# piezo-jfet-buffer-simple-2x.net
KiCad netlist of a schematic drawn in EAGLE
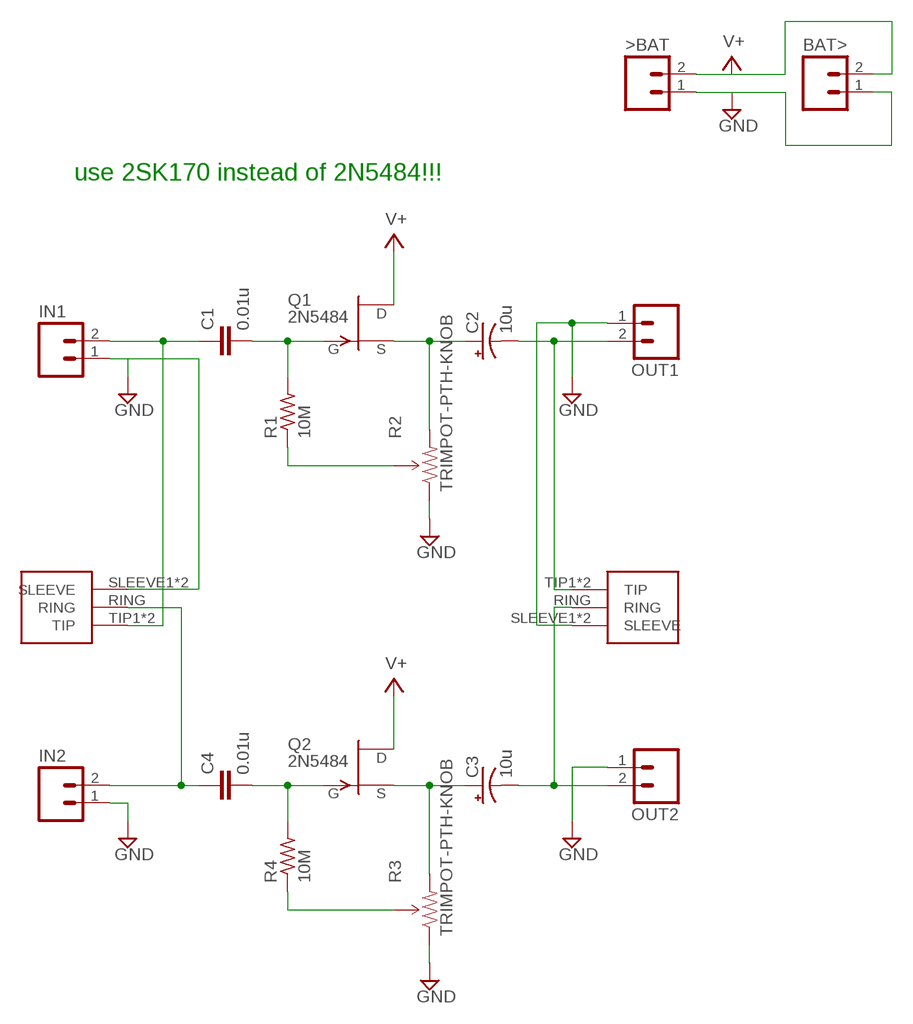
[diagram p0: schematic, sheet 1]

(export (version "E")
  (design (tool "Eeschema 10.0.6"))
  (components
    (comp (ref ">BAT")
      (value "M02PTH")
      (footprint "eagle-import:1X02")
      (libsource (lib "eagle-import") (part "M02PTH"))
    )
    (comp (ref "BAT>")
      (value "M02PTH")
      (footprint "eagle-import:1X02")
      (libsource (lib "eagle-import") (part "M02PTH"))
    )
    (comp (ref "C1")
      (value "0.01u")
      (footprint "eagle-import:C5B3")
      (libsource (lib "eagle-import") (part "C5/3"))
    )
    (comp (ref "C2")
      (value "10u")
      (footprint "eagle-import:CPOL-RADIAL-10UF-25V")
      (libsource (lib "eagle-import") (part "CAP_POLPTH2"))
    )
    (comp (ref "C3")
      (value "10u")
      (footprint "eagle-import:CPOL-RADIAL-10UF-25V")
      (libsource (lib "eagle-import") (part "CAP_POLPTH2"))
    )
    (comp (ref "C4")
      (value "0.01u")
      (footprint "eagle-import:C5B3")
      (libsource (lib "eagle-import") (part "C5/3"))
    )
    (comp (ref "IN1")
      (value "M02LOCK")
      (footprint "eagle-import:1X02_LOCK")
      (libsource (lib "eagle-import") (part "M02LOCK"))
    )
    (comp (ref "IN2")
      (value "M02LOCK")
      (footprint "eagle-import:1X02_LOCK")
      (libsource (lib "eagle-import") (part "M02LOCK"))
    )
    (comp (ref "OUT1")
      (value "M02LOCK")
      (footprint "eagle-import:1X02_LOCK")
      (libsource (lib "eagle-import") (part "M02LOCK"))
    )
    (comp (ref "OUT2")
      (value "M02LOCK")
      (footprint "eagle-import:1X02_LOCK")
      (libsource (lib "eagle-import") (part "M02LOCK"))
    )
    (comp (ref "Q1")
      (value "2N5484")
      (footprint "eagle-import:TO92-")
      (libsource (lib "eagle-import") (part "?5482N4"))
    )
    (comp (ref "Q2")
      (value "2N5484")
      (footprint "eagle-import:TO92-")
      (libsource (lib "eagle-import") (part "?5482N4"))
    )
    (comp (ref "R1")
      (value "10M")
      (footprint "eagle-import:0204V")
      (libsource (lib "eagle-import") (part "R-US_0204/2V"))
    )
    (comp (ref "R2")
      (value "TRIMPOT-PTH-KNOB")
      (footprint "eagle-import:3386U")
      (libsource (lib "eagle-import") (part "TRIMPOT-PTH-KNOB"))
    )
    (comp (ref "R3")
      (value "TRIMPOT-PTH-KNOB")
      (footprint "eagle-import:3386U")
      (libsource (lib "eagle-import") (part "TRIMPOT-PTH-KNOB"))
    )
    (comp (ref "R4")
      (value "10M")
      (footprint "eagle-import:0204V")
      (libsource (lib "eagle-import") (part "R-US_0204/2V"))
    )
    (comp (ref "U$1")
      (value "1/8\"-F-STEREO-PCB")
      (footprint "eagle-import:1_8_-F-STEREO-PCB")
      (libsource (lib "eagle-import") (part "1/8{dblquote}-F-STEREO-PCB"))
    )
    (comp (ref "U$2")
      (value "1/8\"-F-STEREO-PCB")
      (footprint "eagle-import:1_8_-F-STEREO-PCB")
      (libsource (lib "eagle-import") (part "1/8{dblquote}-F-STEREO-PCB"))
    )
  )
  (nets
    (net (code "1") (name "GND") (class "Default")
      (node (ref ">BAT") (pin "1") (pinfunction "1_1") (pintype "passive"))
      (node (ref "BAT>") (pin "1") (pinfunction "1_1") (pintype "passive"))
      (node (ref "IN1") (pin "1") (pinfunction "1_1") (pintype "passive"))
      (node (ref "IN2") (pin "1") (pinfunction "1_1") (pintype "passive"))
      (node (ref "OUT1") (pin "1") (pinfunction "1_1") (pintype "passive"))
      (node (ref "OUT2") (pin "1") (pinfunction "1_1") (pintype "passive"))
      (node (ref "R2") (pin "1") (pinfunction "CCW_1") (pintype "passive"))
      (node (ref "R3") (pin "1") (pinfunction "CCW_1") (pintype "passive"))
      (node (ref "U$1") (pin "SLEEVE1") (pinfunction "SLEEVE_SLEEVE1") (pintype "bidirectional"))
      (node (ref "U$1") (pin "SLEEVE2") (pinfunction "SLEEVE_SLEEVE2") (pintype "bidirectional"))
      (node (ref "U$2") (pin "SLEEVE1") (pinfunction "SLEEVE_SLEEVE1") (pintype "bidirectional"))
      (node (ref "U$2") (pin "SLEEVE2") (pinfunction "SLEEVE_SLEEVE2") (pintype "bidirectional"))
    )
    (net (code "2") (name "Net-(C1-Pad1)") (class "Default")
      (node (ref "C1") (pin "1") (pinfunction "1_1") (pintype "passive"))
      (node (ref "IN1") (pin "2") (pinfunction "2_2") (pintype "passive"))
      (node (ref "U$2") (pin "TIP1") (pinfunction "TIP_TIP1") (pintype "bidirectional"))
      (node (ref "U$2") (pin "TIP2") (pinfunction "TIP_TIP2") (pintype "bidirectional"))
    )
    (net (code "3") (name "Net-(C2-+)") (class "Default")
      (node (ref "C2") (pin "1") (pinfunction "+_1") (pintype "passive"))
      (node (ref "Q1") (pin "2") (pinfunction "S_2") (pintype "passive"))
      (node (ref "R2") (pin "3") (pinfunction "CW_3") (pintype "passive"))
    )
    (net (code "4") (name "Net-(C2--)") (class "Default")
      (node (ref "C2") (pin "2") (pinfunction "-_2") (pintype "passive"))
      (node (ref "OUT1") (pin "2") (pinfunction "2_2") (pintype "passive"))
      (node (ref "U$1") (pin "TIP1") (pinfunction "TIP_TIP1") (pintype "bidirectional"))
      (node (ref "U$1") (pin "TIP2") (pinfunction "TIP_TIP2") (pintype "bidirectional"))
    )
    (net (code "5") (name "Net-(C3-+)") (class "Default")
      (node (ref "C3") (pin "1") (pinfunction "+_1") (pintype "passive"))
      (node (ref "Q2") (pin "2") (pinfunction "S_2") (pintype "passive"))
      (node (ref "R3") (pin "3") (pinfunction "CW_3") (pintype "passive"))
    )
    (net (code "6") (name "Net-(C3--)") (class "Default")
      (node (ref "C3") (pin "2") (pinfunction "-_2") (pintype "passive"))
      (node (ref "OUT2") (pin "2") (pinfunction "2_2") (pintype "passive"))
      (node (ref "U$1") (pin "RING") (pinfunction "RING_RING") (pintype "bidirectional"))
    )
    (net (code "7") (name "Net-(C4-Pad1)") (class "Default")
      (node (ref "C4") (pin "1") (pinfunction "1_1") (pintype "passive"))
      (node (ref "IN2") (pin "2") (pinfunction "2_2") (pintype "passive"))
      (node (ref "U$2") (pin "RING") (pinfunction "RING_RING") (pintype "bidirectional"))
    )
    (net (code "8") (name "Net-(Q1-G)") (class "Default")
      (node (ref "C1") (pin "2") (pinfunction "2_2") (pintype "passive"))
      (node (ref "Q1") (pin "1") (pinfunction "G_1") (pintype "passive"))
      (node (ref "R1") (pin "2") (pinfunction "2_2") (pintype "passive"))
    )
    (net (code "9") (name "Net-(Q2-G)") (class "Default")
      (node (ref "C4") (pin "2") (pinfunction "2_2") (pintype "passive"))
      (node (ref "Q2") (pin "1") (pinfunction "G_1") (pintype "passive"))
      (node (ref "R4") (pin "2") (pinfunction "2_2") (pintype "passive"))
    )
    (net (code "10") (name "Net-(R2-WIPER)") (class "Default")
      (node (ref "R1") (pin "1") (pinfunction "1_1") (pintype "passive"))
      (node (ref "R2") (pin "2") (pinfunction "WIPER_2") (pintype "passive"))
    )
    (net (code "11") (name "Net-(R3-WIPER)") (class "Default")
      (node (ref "R3") (pin "2") (pinfunction "WIPER_2") (pintype "passive"))
      (node (ref "R4") (pin "1") (pinfunction "1_1") (pintype "passive"))
    )
    (net (code "12") (name "V+") (class "Default")
      (node (ref ">BAT") (pin "2") (pinfunction "2_2") (pintype "passive"))
      (node (ref "BAT>") (pin "2") (pinfunction "2_2") (pintype "passive"))
      (node (ref "Q1") (pin "3") (pinfunction "D_3") (pintype "passive"))
      (node (ref "Q2") (pin "3") (pinfunction "D_3") (pintype "passive"))
    )
  )
)
